# Safety_2019_V_3_0_Faults.net
KiCad netlist of a schematic drawn in Altium Designer
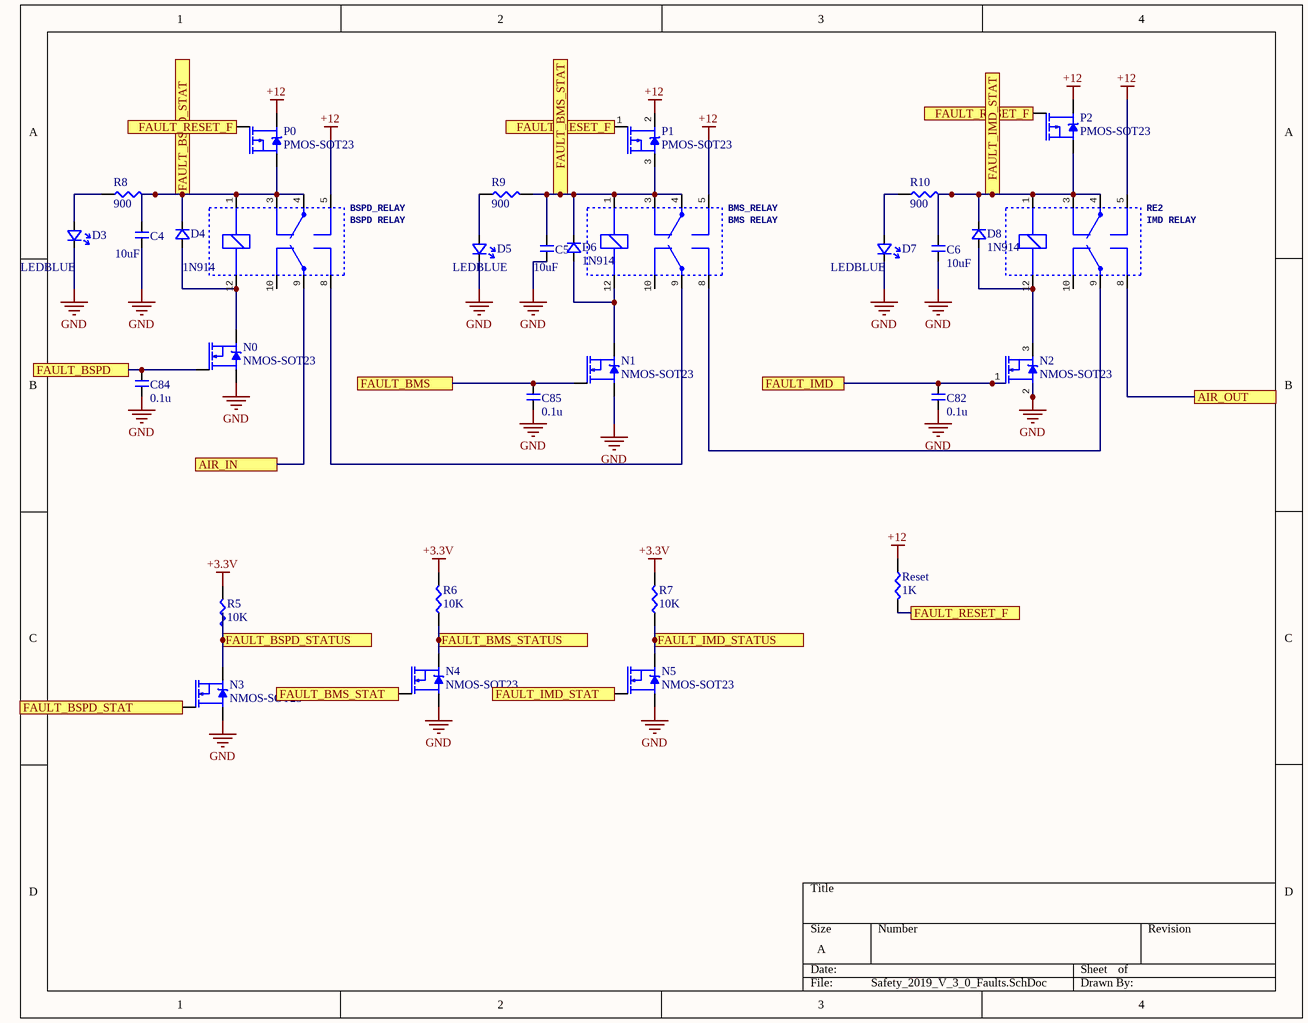
[diagram p0: Safety_2019_V_3_0_Faults.SchDoc]

(export (version "E")
  (design (tool "Eeschema 10.0.6"))
  (components
    (comp (ref "BMS_RELAY")
      (value "BMS RELAY")
      (footprint "RELAY-DPDT_EC2")
      (libsource (lib "ife19_Elec_Library") (part "RELAY_EC2"))
    )
    (comp (ref "BSPD_RELAY")
      (value "BSPD RELAY")
      (footprint "RELAY-DPDT_EC2")
      (libsource (lib "ife19_Elec_Library") (part "RELAY_EC2"))
    )
    (comp (ref "C4")
      (value "10uF")
      (footprint "CAP-0603")
      (libsource (lib "ife19_Elec_Library") (part "CAP-0603"))
    )
    (comp (ref "C5")
      (value "10uF")
      (footprint "CAP-0603")
      (libsource (lib "ife19_Elec_Library") (part "CAP-0603"))
    )
    (comp (ref "C6")
      (value "10uF")
      (footprint "CAP-0603")
      (libsource (lib "ife19_Elec_Library") (part "CAP-0603"))
    )
    (comp (ref "C82")
      (value "0.1u")
      (footprint "CAP-0603")
      (libsource (lib "ife19_Elec_Library") (part "CAP-0603"))
    )
    (comp (ref "C84")
      (value "0.1u")
      (footprint "CAP-0603")
      (libsource (lib "ife19_Elec_Library") (part "CAP-0603"))
    )
    (comp (ref "C85")
      (value "0.1u")
      (footprint "CAP-0603")
      (libsource (lib "ife19_Elec_Library") (part "CAP-0603"))
    )
    (comp (ref "D3")
      (value "LEDBLUE")
      (footprint "LEDBLUE-0603")
      (libsource (lib "ife19_Elec_Library") (part "LEDBLUE-0603"))
    )
    (comp (ref "D4")
      (value "1N914")
      (footprint "DO41-10")
      (libsource (lib "ife19_Elec_Library") (part "DIODE-DO41-10"))
    )
    (comp (ref "D5")
      (value "LEDBLUE")
      (footprint "LEDBLUE-0603")
      (libsource (lib "ife19_Elec_Library") (part "LEDBLUE-0603"))
    )
    (comp (ref "D6")
      (value "1N914")
      (footprint "DO41-10")
      (libsource (lib "ife19_Elec_Library") (part "DIODE-DO41-10"))
    )
    (comp (ref "D7")
      (value "LEDBLUE")
      (footprint "LEDBLUE-0603")
      (libsource (lib "ife19_Elec_Library") (part "LEDBLUE-0603"))
    )
    (comp (ref "D8")
      (value "1N914")
      (footprint "DO41-10")
      (libsource (lib "ife19_Elec_Library") (part "DIODE-DO41-10"))
    )
    (comp (ref "N0")
      (value "NMOS-SOT23")
      (footprint "SOT23")
      (libsource (lib "ife19_Elec_Library") (part "NMOS-SOT23"))
    )
    (comp (ref "N1")
      (value "NMOS-SOT23")
      (footprint "SOT23")
      (libsource (lib "ife19_Elec_Library") (part "NMOS-SOT23"))
    )
    (comp (ref "N2") (value "NMOS-SOT23") (footprint "SOT23") (libsource (lib "") (part "NMOS-SOT23_1")))
    (comp (ref "N3")
      (value "NMOS-SOT23")
      (footprint "SOT23")
      (libsource (lib "ife19_Elec_Library") (part "NMOS-SOT23"))
    )
    (comp (ref "N4")
      (value "NMOS-SOT23")
      (footprint "SOT23")
      (libsource (lib "ife19_Elec_Library") (part "NMOS-SOT23"))
    )
    (comp (ref "N5")
      (value "NMOS-SOT23")
      (footprint "SOT23")
      (libsource (lib "ife19_Elec_Library") (part "NMOS-SOT23"))
    )
    (comp (ref "P0")
      (value "PMOS-SOT23")
      (footprint "SOT23")
      (libsource (lib "ife19_Elec_Library") (part "PMOS-SOT23"))
    )
    (comp (ref "P1") (value "PMOS-SOT23") (footprint "SOT23") (libsource (lib "") (part "PMOS-SOT23_1")))
    (comp (ref "P2")
      (value "PMOS-SOT23")
      (footprint "SOT23")
      (libsource (lib "ife19_Elec_Library") (part "PMOS-SOT23"))
    )
    (comp (ref "R5")
      (value "10K")
      (footprint "RES-0603")
      (libsource (lib "ife19_Elec_Library") (part "RES-0603"))
    )
    (comp (ref "R6")
      (value "10K")
      (footprint "RES-0603")
      (libsource (lib "ife19_Elec_Library") (part "RES-0603"))
    )
    (comp (ref "R7")
      (value "10K")
      (footprint "RES-0603")
      (libsource (lib "ife19_Elec_Library") (part "RES-0603"))
    )
    (comp (ref "R8")
      (value "900")
      (footprint "RES-0603")
      (libsource (lib "ife19_Elec_Library") (part "RES-0603"))
    )
    (comp (ref "R9")
      (value "900")
      (footprint "RES-0603")
      (libsource (lib "ife19_Elec_Library") (part "RES-0603"))
    )
    (comp (ref "R10")
      (value "900")
      (footprint "RES-0603")
      (libsource (lib "ife19_Elec_Library") (part "RES-0603"))
    )
    (comp (ref "RE2")
      (value "IMD RELAY")
      (footprint "RELAY-DPDT_EC2")
      (libsource (lib "ife19_Elec_Library") (part "RELAY_EC2"))
    )
    (comp (ref "Reset")
      (value "1K")
      (footprint "RES-0603")
      (libsource (lib "ife19_Elec_Library") (part "RES-0603"))
    )
  )
  (nets
    (net (code "1") (name "+3.3V") (class "Default")
      (node (ref "R5") (pin "2") (pinfunction "2_2") (pintype "passive"))
      (node (ref "R6") (pin "2") (pinfunction "2_2") (pintype "passive"))
      (node (ref "R7") (pin "2") (pinfunction "2_2") (pintype "passive"))
    )
    (net (code "2") (name "+12") (class "Default")
      (node (ref "BMS_RELAY") (pin "5") (pintype "passive"))
      (node (ref "BSPD_RELAY") (pin "5") (pintype "passive"))
      (node (ref "P0") (pin "2") (pinfunction "S_2") (pintype "passive"))
      (node (ref "P1") (pin "2") (pinfunction "S_2") (pintype "passive"))
      (node (ref "P2") (pin "2") (pinfunction "S_2") (pintype "passive"))
      (node (ref "RE2") (pin "5") (pintype "passive"))
      (node (ref "Reset") (pin "1") (pinfunction "1_1") (pintype "passive"))
    )
    (net (code "3") (name "/AIR_IN") (class "Default")
      (node (ref "BSPD_RELAY") (pin "9") (pintype "passive"))
    )
    (net (code "4") (name "/AIR_OUT") (class "Default") (node (ref "RE2") (pin "8") (pintype "passive")))
    (net (code "5") (name "/FAULT_BMS") (class "Default")
      (node (ref "C85") (pin "2") (pinfunction "2_2") (pintype "passive"))
      (node (ref "N1") (pin "1") (pinfunction "G_1") (pintype "passive"))
    )
    (net (code "6") (name "/FAULT_BMS_STAT") (class "Default")
      (node (ref "BMS_RELAY") (pin "1") (pintype "passive"))
      (node (ref "BMS_RELAY") (pin "3") (pintype "passive"))
      (node (ref "BMS_RELAY") (pin "4") (pintype "passive"))
      (node (ref "C5") (pin "1") (pinfunction "1_1") (pintype "passive"))
      (node (ref "D6") (pin "K") (pinfunction "K_K") (pintype "passive"))
      (node (ref "N4") (pin "1") (pinfunction "G_1") (pintype "passive"))
      (node (ref "P1") (pin "3") (pinfunction "D_3") (pintype "passive"))
      (node (ref "R9") (pin "2") (pinfunction "2_2") (pintype "passive"))
    )
    (net (code "7") (name "/FAULT_BMS_STATUS") (class "Default")
      (node (ref "N4") (pin "3") (pinfunction "D_3") (pintype "passive"))
      (node (ref "R6") (pin "1") (pinfunction "1_1") (pintype "passive"))
    )
    (net (code "8") (name "/FAULT_BSPD") (class "Default")
      (node (ref "C84") (pin "2") (pinfunction "2_2") (pintype "passive"))
      (node (ref "N0") (pin "1") (pinfunction "G_1") (pintype "passive"))
    )
    (net (code "9") (name "/FAULT_BSPD_STAT") (class "Default")
      (node (ref "BSPD_RELAY") (pin "1") (pintype "passive"))
      (node (ref "BSPD_RELAY") (pin "3") (pintype "passive"))
      (node (ref "BSPD_RELAY") (pin "4") (pintype "passive"))
      (node (ref "C4") (pin "1") (pinfunction "1_1") (pintype "passive"))
      (node (ref "D4") (pin "K") (pinfunction "K_K") (pintype "passive"))
      (node (ref "N3") (pin "1") (pinfunction "G_1") (pintype "passive"))
      (node (ref "P0") (pin "3") (pinfunction "D_3") (pintype "passive"))
      (node (ref "R8") (pin "2") (pinfunction "2_2") (pintype "passive"))
    )
    (net (code "10") (name "/FAULT_BSPD_STATUS") (class "Default")
      (node (ref "N3") (pin "3") (pinfunction "D_3") (pintype "passive"))
      (node (ref "R5") (pin "1") (pinfunction "1_1") (pintype "passive"))
    )
    (net (code "11") (name "/FAULT_IMD") (class "Default")
      (node (ref "C82") (pin "2") (pinfunction "2_2") (pintype "passive"))
      (node (ref "N2") (pin "1") (pinfunction "G_1") (pintype "passive"))
    )
    (net (code "12") (name "/FAULT_IMD_STAT") (class "Default")
      (node (ref "C6") (pin "1") (pinfunction "1_1") (pintype "passive"))
      (node (ref "D8") (pin "K") (pinfunction "K_K") (pintype "passive"))
      (node (ref "N5") (pin "1") (pinfunction "G_1") (pintype "passive"))
      (node (ref "P2") (pin "3") (pinfunction "D_3") (pintype "passive"))
      (node (ref "R10") (pin "2") (pinfunction "2_2") (pintype "passive"))
      (node (ref "RE2") (pin "1") (pintype "passive"))
      (node (ref "RE2") (pin "3") (pintype "passive"))
      (node (ref "RE2") (pin "4") (pintype "passive"))
    )
    (net (code "13") (name "/FAULT_IMD_STATUS") (class "Default")
      (node (ref "N5") (pin "3") (pinfunction "D_3") (pintype "passive"))
      (node (ref "R7") (pin "1") (pinfunction "1_1") (pintype "passive"))
    )
    (net (code "14") (name "/FAULT_RESET_F") (class "Default")
      (node (ref "P0") (pin "1") (pinfunction "G_1") (pintype "passive"))
      (node (ref "P1") (pin "1") (pinfunction "G_1") (pintype "passive"))
      (node (ref "P2") (pin "1") (pinfunction "G_1") (pintype "passive"))
      (node (ref "Reset") (pin "2") (pinfunction "2_2") (pintype "passive"))
    )
    (net (code "15") (name "GND") (class "Default")
      (node (ref "C4") (pin "2") (pinfunction "2_2") (pintype "passive"))
      (node (ref "C5") (pin "2") (pinfunction "2_2") (pintype "passive"))
      (node (ref "C6") (pin "2") (pinfunction "2_2") (pintype "passive"))
      (node (ref "C82") (pin "1") (pinfunction "1_1") (pintype "passive"))
      (node (ref "C84") (pin "1") (pinfunction "1_1") (pintype "passive"))
      (node (ref "C85") (pin "1") (pinfunction "1_1") (pintype "passive"))
      (node (ref "D3") (pin "K") (pinfunction "K_K") (pintype "passive"))
      (node (ref "D5") (pin "K") (pinfunction "K_K") (pintype "passive"))
      (node (ref "D7") (pin "K") (pinfunction "K_K") (pintype "passive"))
      (node (ref "N0") (pin "2") (pinfunction "S_2") (pintype "passive"))
      (node (ref "N1") (pin "2") (pinfunction "S_2") (pintype "passive"))
      (node (ref "N2") (pin "2") (pinfunction "S_2") (pintype "passive"))
      (node (ref "N3") (pin "2") (pinfunction "S_2") (pintype "passive"))
      (node (ref "N4") (pin "2") (pinfunction "S_2") (pintype "passive"))
      (node (ref "N5") (pin "2") (pinfunction "S_2") (pintype "passive"))
    )
    (net (code "16") (name "Net-(BMS_RELAY-Pad8)") (class "Default")
      (node (ref "BMS_RELAY") (pin "8") (pintype "passive"))
      (node (ref "RE2") (pin "9") (pintype "passive"))
    )
    (net (code "17") (name "Net-(BMS_RELAY-Pad9)") (class "Default")
      (node (ref "BMS_RELAY") (pin "9") (pintype "passive"))
      (node (ref "BSPD_RELAY") (pin "8") (pintype "passive"))
    )
    (net (code "18") (name "Net-(D3-PadA)") (class "Default")
      (node (ref "D3") (pin "A") (pinfunction "A_A") (pintype "passive"))
      (node (ref "R8") (pin "1") (pinfunction "1_1") (pintype "passive"))
    )
    (net (code "19") (name "Net-(D5-PadA)") (class "Default")
      (node (ref "D5") (pin "A") (pinfunction "A_A") (pintype "passive"))
      (node (ref "R9") (pin "1") (pinfunction "1_1") (pintype "passive"))
    )
    (net (code "20") (name "Net-(D7-PadA)") (class "Default")
      (node (ref "D7") (pin "A") (pinfunction "A_A") (pintype "passive"))
      (node (ref "R10") (pin "1") (pinfunction "1_1") (pintype "passive"))
    )
    (net (code "21") (name "Net-(N0-D)") (class "Default")
      (node (ref "BSPD_RELAY") (pin "12") (pintype "passive"))
      (node (ref "D4") (pin "A") (pinfunction "A_A") (pintype "passive"))
      (node (ref "N0") (pin "3") (pinfunction "D_3") (pintype "passive"))
    )
    (net (code "22") (name "Net-(N1-D)") (class "Default")
      (node (ref "BMS_RELAY") (pin "12") (pintype "passive"))
      (node (ref "D6") (pin "A") (pinfunction "A_A") (pintype "passive"))
      (node (ref "N1") (pin "3") (pinfunction "D_3") (pintype "passive"))
    )
    (net (code "23") (name "Net-(N2-D)") (class "Default")
      (node (ref "D8") (pin "A") (pinfunction "A_A") (pintype "passive"))
      (node (ref "N2") (pin "3") (pinfunction "D_3") (pintype "passive"))
      (node (ref "RE2") (pin "12") (pintype "passive"))
    )
    (net (code "24") (name "unconnected-(BMS_RELAY-Pad10)") (class "Default")
      (node (ref "BMS_RELAY") (pin "10") (pintype "passive"))
    )
    (net (code "25") (name "unconnected-(BSPD_RELAY-Pad10)") (class "Default")
      (node (ref "BSPD_RELAY") (pin "10") (pintype "passive"))
    )
    (net (code "26") (name "unconnected-(RE2-Pad10)") (class "Default")
      (node (ref "RE2") (pin "10") (pintype "passive"))
    )
  )
)
